# cc3100-breakout.net
KiCad netlist of a schematic drawn in EAGLE
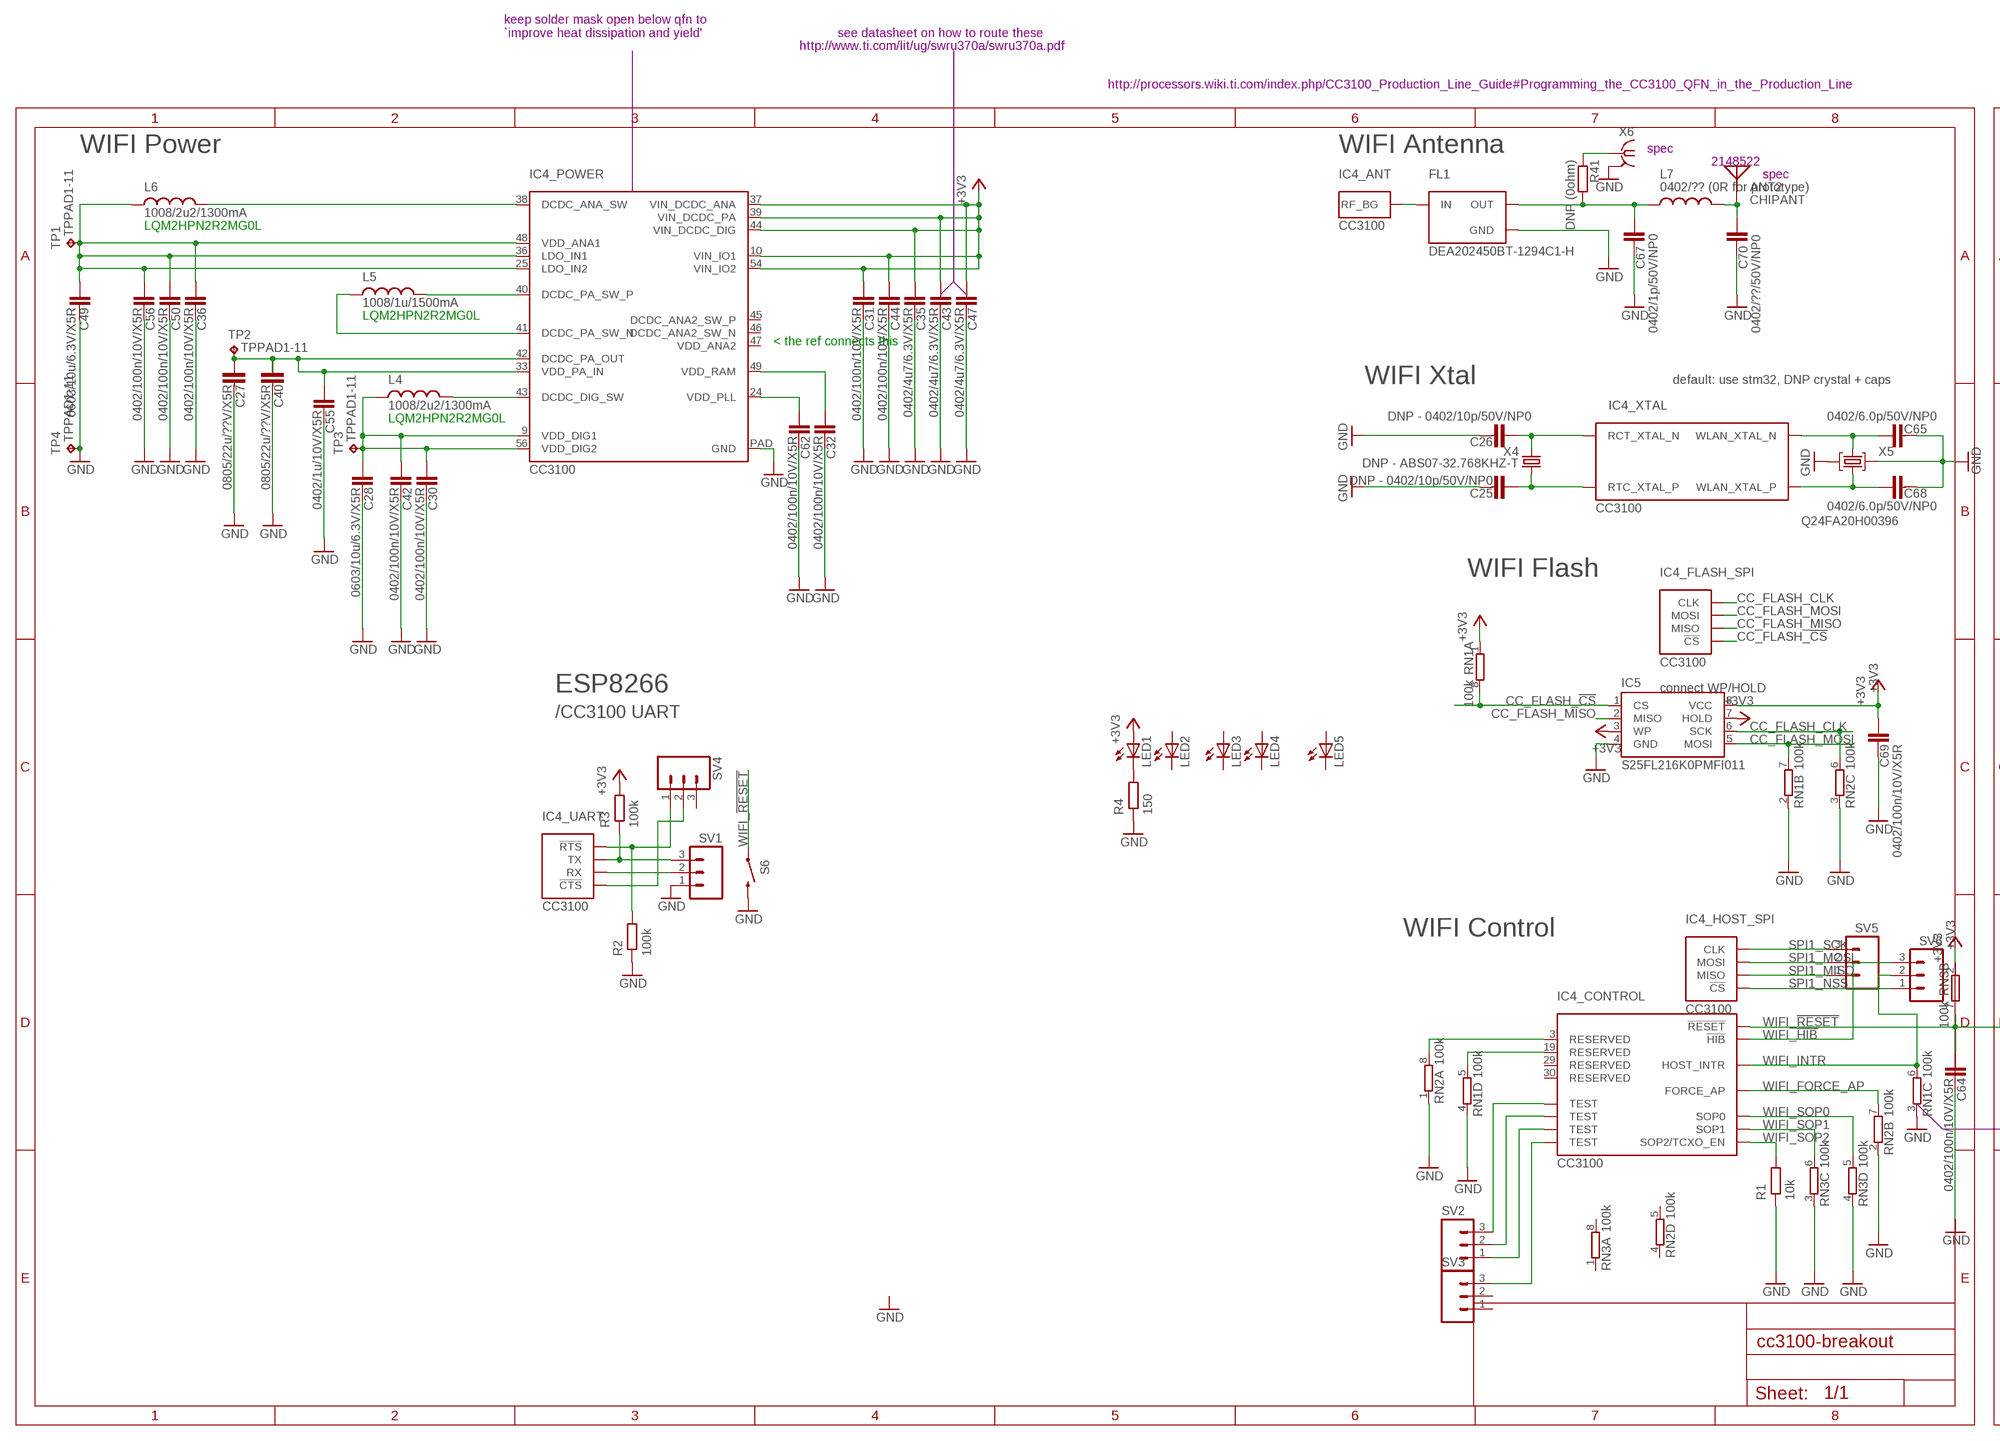
[diagram p0: schematic, sheet 1, part 1 of 2]
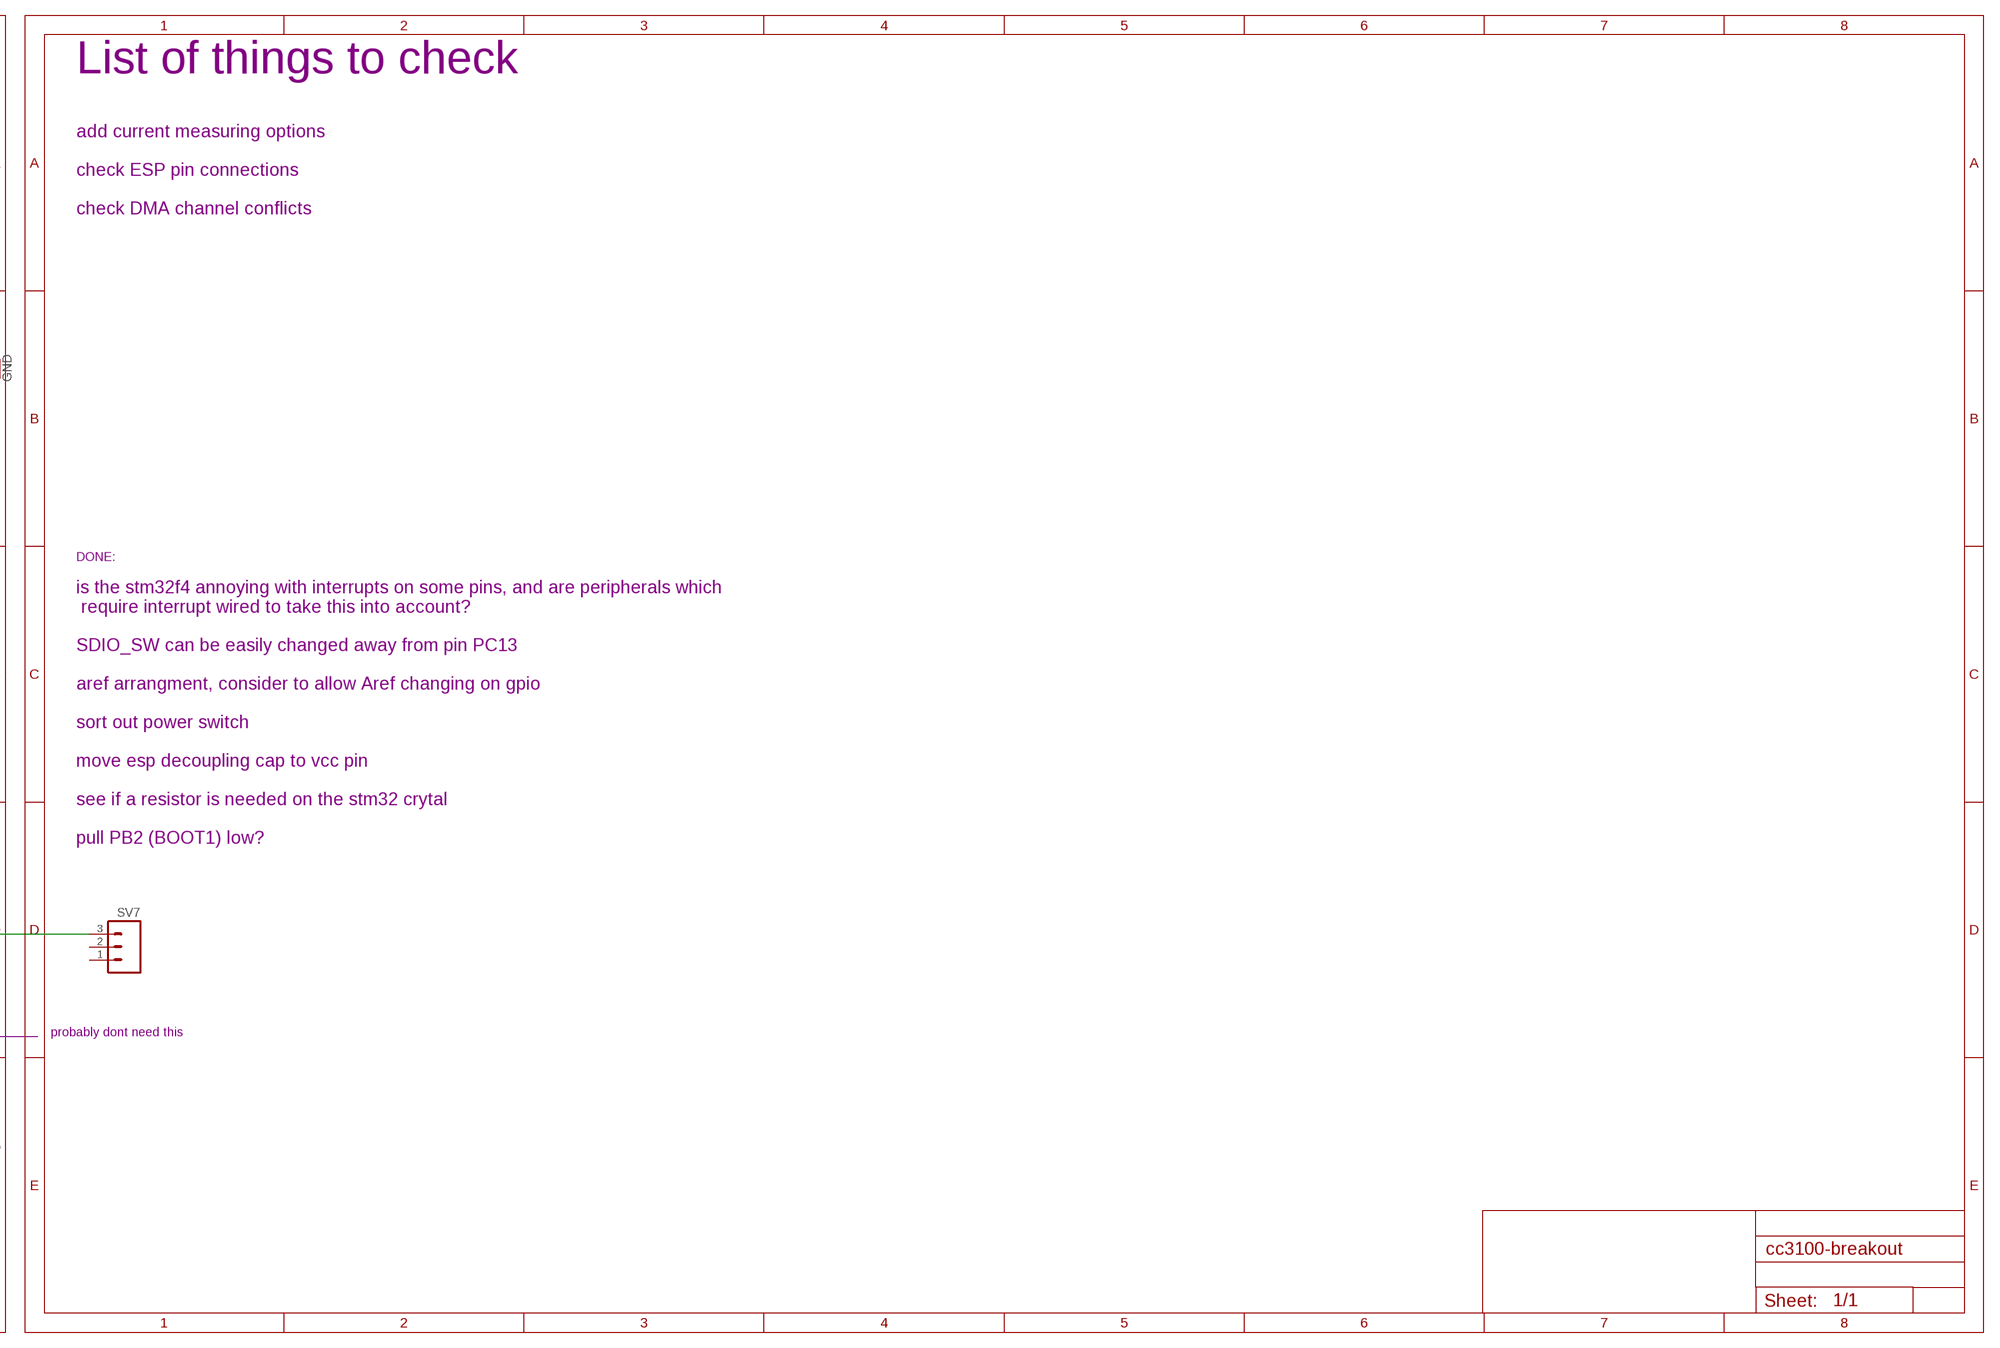
[diagram p1: schematic, sheet 1, part 2 of 2]

(export (version "E")
  (design (tool "Eeschema 10.0.6"))
  (components
    (comp (ref "ANT2")
      (value "CHIPANT")
      (footprint "eagle-import:2450AT42A100")
      (libsource (lib "eagle-import") (part "CHIPANT"))
    )
    (comp (ref "C25")
      (value "DNP - 0402/10p/50V/NP0")
      (footprint "eagle-import:C0603-N")
      (libsource (lib "eagle-import") (part "CAPACITOR0603-N"))
    )
    (comp (ref "C26")
      (value "DNP - 0402/10p/50V/NP0")
      (footprint "eagle-import:C0603-N")
      (libsource (lib "eagle-import") (part "CAPACITOR0603-N"))
    )
    (comp (ref "C27")
      (value "0805/22u/??V/X5R")
      (footprint "eagle-import:C0805-N")
      (libsource (lib "eagle-import") (part "CAPACITOR0805-N"))
    )
    (comp (ref "C28")
      (value "0603/10u/6.3V/X5R")
      (footprint "eagle-import:C0603K-SMALL")
      (libsource (lib "eagle-import") (part "C-EUC0603K-SMALL"))
    )
    (comp (ref "C30")
      (value "0402/100n/10V/X5R")
      (footprint "eagle-import:C0402-SMALLER")
      (libsource (lib "eagle-import") (part "C-EUC0402-SMALLER"))
    )
    (comp (ref "C31")
      (value "0402/100n/10V/X5R")
      (footprint "eagle-import:C0402-SMALLER")
      (libsource (lib "eagle-import") (part "C-EUC0402-SMALLER"))
    )
    (comp (ref "C32")
      (value "0402/100n/10V/X5R")
      (footprint "eagle-import:C0402-SMALLER")
      (libsource (lib "eagle-import") (part "C-EUC0402-SMALLER"))
    )
    (comp (ref "C35")
      (value "0402/4u7/6.3V/X5R")
      (footprint "eagle-import:C0402-SMALLER")
      (libsource (lib "eagle-import") (part "C-EUC0402-SMALLER"))
    )
    (comp (ref "C36")
      (value "0402/100n/10V/X5R")
      (footprint "eagle-import:C0402-SMALLER")
      (libsource (lib "eagle-import") (part "C-EUC0402-SMALLER"))
    )
    (comp (ref "C40")
      (value "0805/22u/??V/X5R")
      (footprint "eagle-import:C0805-N")
      (libsource (lib "eagle-import") (part "CAPACITOR0805-N"))
    )
    (comp (ref "C42")
      (value "0402/100n/10V/X5R")
      (footprint "eagle-import:C0402-SMALLER")
      (libsource (lib "eagle-import") (part "C-EUC0402-SMALLER"))
    )
    (comp (ref "C43")
      (value "0402/4u7/6.3V/X5R")
      (footprint "eagle-import:C0402-SMALLER")
      (libsource (lib "eagle-import") (part "C-EUC0402-SMALLER"))
    )
    (comp (ref "C44")
      (value "0402/100n/10V/X5R")
      (footprint "eagle-import:C0402-SMALLER")
      (libsource (lib "eagle-import") (part "C-EUC0402-SMALLER"))
    )
    (comp (ref "C47")
      (value "0402/4u7/6.3V/X5R")
      (footprint "eagle-import:C0402-SMALLER")
      (libsource (lib "eagle-import") (part "C-EUC0402-SMALLER"))
    )
    (comp (ref "C49")
      (value "0603/10u/6.3V/X5R")
      (footprint "eagle-import:C0603K-SMALL")
      (libsource (lib "eagle-import") (part "C-EUC0603K-SMALL"))
    )
    (comp (ref "C50")
      (value "0402/100n/10V/X5R")
      (footprint "eagle-import:C0402-SMALLER")
      (libsource (lib "eagle-import") (part "C-EUC0402-SMALLER"))
    )
    (comp (ref "C55")
      (value "0402/1u/10V/X5R")
      (footprint "eagle-import:C0402-SMALLER")
      (libsource (lib "eagle-import") (part "C-EUC0402-SMALLER"))
    )
    (comp (ref "C56")
      (value "0402/100n/10V/X5R")
      (footprint "eagle-import:C0402-SMALLER")
      (libsource (lib "eagle-import") (part "C-EUC0402-SMALLER"))
    )
    (comp (ref "C62")
      (value "0402/100n/10V/X5R")
      (footprint "eagle-import:C0402-SMALLER")
      (libsource (lib "eagle-import") (part "C-EUC0402-SMALLER"))
    )
    (comp (ref "C64")
      (value "0402/100n/10V/X5R")
      (footprint "eagle-import:C0402-SMALLER")
      (libsource (lib "eagle-import") (part "C-EUC0402-SMALLER"))
    )
    (comp (ref "C65")
      (value "0402/6.0p/50V/NP0")
      (footprint "eagle-import:C0603-N")
      (libsource (lib "eagle-import") (part "CAPACITOR0603-N"))
    )
    (comp (ref "C67")
      (value "0402/1p/50V/NP0")
      (footprint "eagle-import:C0402-SMALLER")
      (libsource (lib "eagle-import") (part "C-EUC0402-SMALLER"))
    )
    (comp (ref "C68")
      (value "0402/6.0p/50V/NP0")
      (footprint "eagle-import:C0603-N")
      (libsource (lib "eagle-import") (part "CAPACITOR0603-N"))
    )
    (comp (ref "C69")
      (value "0402/100n/10V/X5R")
      (footprint "eagle-import:C0402-SMALLER")
      (libsource (lib "eagle-import") (part "C-EUC0402-SMALLER"))
    )
    (comp (ref "C70")
      (value "0402/??/50V/NP0")
      (footprint "eagle-import:C0402-SMALLER")
      (libsource (lib "eagle-import") (part "C-EUC0402-SMALLER"))
    )
    (comp (ref "FL1")
      (value "DEA202450BT-1294C1-H")
      (footprint "eagle-import:DEA202450BT")
      (libsource (lib "eagle-import") (part "DEA202450BT-1294C1-H"))
    )
    (comp (ref "IC4")
      (value "CC3100")
      (footprint "eagle-import:VQFN-64")
      (libsource (lib "eagle-import") (part "CC3100"))
    )
    (comp (ref "IC5")
      (value "S25FL216K0PMFI011")
      (footprint "eagle-import:SO08-EIAJ")
      (libsource (lib "eagle-import") (part "SPI_FLASH-X25XXSMD1"))
    )
    (comp (ref "L4")
      (value "1008/2u2/1300mA")
      (footprint "eagle-import:1008")
      (libsource (lib "eagle-import") (part "INDUCTOR1008"))
    )
    (comp (ref "L5")
      (value "1008/1u/1500mA")
      (footprint "eagle-import:1008")
      (libsource (lib "eagle-import") (part "INDUCTOR1008"))
    )
    (comp (ref "L6")
      (value "1008/2u2/1300mA")
      (footprint "eagle-import:1008")
      (libsource (lib "eagle-import") (part "INDUCTOR1008"))
    )
    (comp (ref "L7")
      (value "0402/?? (0R for prototype)")
      (footprint "eagle-import:L0402")
      (libsource (lib "eagle-import") (part "INDUCTOR-0402-NARROW"))
    )
    (comp (ref "LED1")
      (value "LEDCHIPLED_0603")
      (footprint "eagle-import:CHIPLED_0603")
      (libsource (lib "eagle-import") (part "LEDCHIPLED_0603"))
    )
    (comp (ref "LED2")
      (value "LEDCHIPLED_0603")
      (footprint "eagle-import:CHIPLED_0603")
      (libsource (lib "eagle-import") (part "LEDCHIPLED_0603"))
    )
    (comp (ref "LED3")
      (value "LEDCHIPLED_0603")
      (footprint "eagle-import:CHIPLED_0603")
      (libsource (lib "eagle-import") (part "LEDCHIPLED_0603"))
    )
    (comp (ref "LED4")
      (value "LEDCHIPLED_0603")
      (footprint "eagle-import:CHIPLED_0603")
      (libsource (lib "eagle-import") (part "LEDCHIPLED_0603"))
    )
    (comp (ref "LED5")
      (value "LEDCHIPLED_0603")
      (footprint "eagle-import:CHIPLED_0603")
      (libsource (lib "eagle-import") (part "LEDCHIPLED_0603"))
    )
    (comp (ref "R1")
      (value "10k")
      (footprint "eagle-import:R0603-N")
      (libsource (lib "eagle-import") (part "RESISTOR0603-N"))
    )
    (comp (ref "R2")
      (value "100k")
      (footprint "eagle-import:R0603-N")
      (libsource (lib "eagle-import") (part "RESISTOR0603-N"))
    )
    (comp (ref "R3")
      (value "100k")
      (footprint "eagle-import:R0603-N")
      (libsource (lib "eagle-import") (part "RESISTOR0603-N"))
    )
    (comp (ref "R4")
      (value "150")
      (footprint "eagle-import:R0603-N")
      (libsource (lib "eagle-import") (part "RESISTOR0603-N"))
    )
    (comp (ref "R41")
      (value "DNP (0ohm)")
      (footprint "eagle-import:R0402-SMALLER")
      (libsource (lib "eagle-import") (part "R-EU_R0402-SMALLER"))
    )
    (comp (ref "RN1")
      (value "100k")
      (footprint "eagle-import:EXB38V")
      (libsource (lib "eagle-import") (part "4R-NEXB38V"))
    )
    (comp (ref "RN2")
      (value "100k")
      (footprint "eagle-import:EXB38V")
      (libsource (lib "eagle-import") (part "4R-NEXB38V"))
    )
    (comp (ref "RN3")
      (value "100k")
      (footprint "eagle-import:EXB38V")
      (libsource (lib "eagle-import") (part "4R-NEXB38V"))
    )
    (comp (ref "S6")
      (value "SWITCH-MOMENTARY-2SMD-1101NE")
      (footprint "eagle-import:TACTILE-SWITCH-1101NE")
      (libsource (lib "eagle-import") (part "SWITCH-MOMENTARY-2SMD-1101NE"))
    )
    (comp (ref "SV1")
      (value "M03PTH")
      (footprint "eagle-import:1X03")
      (libsource (lib "eagle-import") (part "M03PTH"))
    )
    (comp (ref "SV2")
      (value "M03PTH")
      (footprint "eagle-import:1X03")
      (libsource (lib "eagle-import") (part "M03PTH"))
    )
    (comp (ref "SV3")
      (value "M03PTH")
      (footprint "eagle-import:1X03")
      (libsource (lib "eagle-import") (part "M03PTH"))
    )
    (comp (ref "SV4")
      (value "M03PTH")
      (footprint "eagle-import:1X03")
      (libsource (lib "eagle-import") (part "M03PTH"))
    )
    (comp (ref "SV5")
      (value "M03PTH")
      (footprint "eagle-import:1X03")
      (libsource (lib "eagle-import") (part "M03PTH"))
    )
    (comp (ref "SV6")
      (value "M03PTH")
      (footprint "eagle-import:1X03")
      (libsource (lib "eagle-import") (part "M03PTH"))
    )
    (comp (ref "SV7")
      (value "M03PTH")
      (footprint "eagle-import:1X03")
      (libsource (lib "eagle-import") (part "M03PTH"))
    )
    (comp (ref "TP1")
      (value "TPPAD1-11")
      (footprint "eagle-import:P1-11")
      (libsource (lib "eagle-import") (part "TPPAD1-11"))
    )
    (comp (ref "TP2")
      (value "TPPAD1-11")
      (footprint "eagle-import:P1-11")
      (libsource (lib "eagle-import") (part "TPPAD1-11"))
    )
    (comp (ref "TP3")
      (value "TPPAD1-11")
      (footprint "eagle-import:P1-11")
      (libsource (lib "eagle-import") (part "TPPAD1-11"))
    )
    (comp (ref "TP4")
      (value "TPPAD1-11")
      (footprint "eagle-import:P1-11")
      (libsource (lib "eagle-import") (part "TPPAD1-11"))
    )
    (comp (ref "X4")
      (value "DNP - ABS07-32.768KHZ-T")
      (footprint "eagle-import:RESONATOR_EPSON_FC_145")
      (libsource (lib "eagle-import") (part "RESONATOR_EPSON_FC_145"))
    )
    (comp (ref "X5")
      (value "Q24FA20H00396")
      (footprint "eagle-import:CRYSTAL-2.5X2.0")
      (libsource (lib "eagle-import") (part "CRYSTAL-2.5X2.0"))
    )
    (comp (ref "X6")
      (value "MC-921")
      (footprint "eagle-import:MC-921")
      (libsource (lib "eagle-import") (part "MC-921"))
    )
  )
  (nets
    (net (code "1") (name "+3V3") (class "Default")
      (node (ref "C31") (pin "2") (pinfunction "2_2") (pintype "passive"))
      (node (ref "C35") (pin "2") (pinfunction "2_2") (pintype "passive"))
      (node (ref "C43") (pin "2") (pinfunction "2_2") (pintype "passive"))
      (node (ref "C44") (pin "2") (pinfunction "2_2") (pintype "passive"))
      (node (ref "C47") (pin "2") (pinfunction "2_2") (pintype "passive"))
      (node (ref "C69") (pin "2") (pinfunction "2_2") (pintype "passive"))
      (node (ref "IC4") (pin "10") (pinfunction "VIN_IO1_10") (pintype "bidirectional"))
      (node (ref "IC4") (pin "37") (pinfunction "VIN_DCDC_ANA_37") (pintype "bidirectional"))
      (node (ref "IC4") (pin "39") (pinfunction "VIN_DCDC_PA_39") (pintype "bidirectional"))
      (node (ref "IC4") (pin "44") (pinfunction "VIN_DCDC_DIG_44") (pintype "bidirectional"))
      (node (ref "IC4") (pin "54") (pinfunction "VIN_IO2_54") (pintype "bidirectional"))
      (node (ref "IC5") (pin "3") (pinfunction "WP_3") (pintype "bidirectional"))
      (node (ref "IC5") (pin "7") (pinfunction "HOLD_7") (pintype "bidirectional"))
      (node (ref "IC5") (pin "8") (pinfunction "VCC_8") (pintype "bidirectional"))
      (node (ref "LED1") (pin "A") (pinfunction "A_A") (pintype "passive"))
      (node (ref "R3") (pin "2") (pinfunction "P$2_2") (pintype "passive"))
      (node (ref "RN1") (pin "1") (pinfunction "1_1") (pintype "passive"))
      (node (ref "RN3") (pin "2") (pinfunction "1_2") (pintype "passive"))
    )
    (net (code "2") (name "/CC_FLASH_CLK") (class "Default")
      (node (ref "IC4") (pin "11") (pinfunction "CLK_11") (pintype "bidirectional"))
      (node (ref "IC5") (pin "6") (pinfunction "SCK_6") (pintype "bidirectional"))
      (node (ref "RN2") (pin "6") (pinfunction "2_6") (pintype "passive"))
    )
    (net (code "3") (name "/CC_FLASH_MISO") (class "Default")
      (node (ref "IC4") (pin "13") (pinfunction "MISO_13") (pintype "bidirectional"))
      (node (ref "IC5") (pin "2") (pinfunction "MISO_2") (pintype "bidirectional"))
    )
    (net (code "4") (name "/CC_FLASH_MOSI") (class "Default")
      (node (ref "IC4") (pin "12") (pinfunction "MOSI_12") (pintype "bidirectional"))
      (node (ref "IC5") (pin "5") (pinfunction "MOSI_5") (pintype "bidirectional"))
      (node (ref "RN1") (pin "7") (pinfunction "2_7") (pintype "passive"))
    )
    (net (code "5") (name "/CC_FLASH_~{CS}") (class "Default")
      (node (ref "IC4") (pin "14") (pinfunction "~{CS}_14") (pintype "bidirectional"))
      (node (ref "IC5") (pin "1") (pinfunction "CS_1") (pintype "bidirectional"))
      (node (ref "RN1") (pin "8") (pinfunction "2_8") (pintype "passive"))
    )
    (net (code "6") (name "/SPI1_MISO") (class "Default")
      (node (ref "IC4") (pin "7") (pinfunction "MISO_7") (pintype "bidirectional"))
      (node (ref "SV5") (pin "1") (pinfunction "1_1") (pintype "passive"))
    )
    (net (code "7") (name "/SPI1_MOSI") (class "Default")
      (node (ref "IC4") (pin "6") (pinfunction "MOSI_6") (pintype "bidirectional"))
      (node (ref "SV5") (pin "2") (pinfunction "2_2") (pintype "passive"))
    )
    (net (code "8") (name "/SPI1_NSS") (class "Default")
      (node (ref "IC4") (pin "8") (pinfunction "~{CS}_8") (pintype "bidirectional"))
      (node (ref "SV6") (pin "1") (pinfunction "1_1") (pintype "passive"))
    )
    (net (code "9") (name "/SPI1_SCK") (class "Default")
      (node (ref "IC4") (pin "5") (pinfunction "CLK_5") (pintype "bidirectional"))
      (node (ref "SV5") (pin "3") (pinfunction "3_3") (pintype "passive"))
    )
    (net (code "10") (name "/WIFI_FORCE_AP") (class "Default")
      (node (ref "IC4") (pin "4") (pinfunction "FORCE_AP_4") (pintype "bidirectional"))
      (node (ref "RN2") (pin "7") (pinfunction "2_7") (pintype "passive"))
    )
    (net (code "11") (name "/WIFI_INTR") (class "Default")
      (node (ref "IC4") (pin "15") (pinfunction "HOST_INTR_15") (pintype "bidirectional"))
      (node (ref "RN1") (pin "6") (pinfunction "2_6") (pintype "passive"))
      (node (ref "SV6") (pin "2") (pinfunction "2_2") (pintype "passive"))
    )
    (net (code "12") (name "/WIFI_SOP0") (class "Default")
      (node (ref "IC4") (pin "35") (pinfunction "SOP0_35") (pintype "bidirectional"))
      (node (ref "RN3") (pin "5") (pinfunction "2_5") (pintype "passive"))
    )
    (net (code "13") (name "/WIFI_SOP1") (class "Default")
      (node (ref "IC4") (pin "34") (pinfunction "SOP1_34") (pintype "bidirectional"))
      (node (ref "RN3") (pin "6") (pinfunction "2_6") (pintype "passive"))
    )
    (net (code "14") (name "/WIFI_SOP2") (class "Default")
      (node (ref "IC4") (pin "21") (pinfunction "SOP2/TCXO_EN_21") (pintype "bidirectional"))
      (node (ref "R1") (pin "2") (pinfunction "P$2_2") (pintype "passive"))
    )
    (net (code "15") (name "/WIFI_~{HIB}") (class "Default")
      (node (ref "IC4") (pin "2") (pinfunction "~{HIB}_2") (pintype "bidirectional"))
      (node (ref "SV6") (pin "3") (pinfunction "3_3") (pintype "passive"))
    )
    (net (code "16") (name "/WIFI_~{RESET}") (class "Default")
      (node (ref "C64") (pin "2") (pinfunction "2_2") (pintype "passive"))
      (node (ref "IC4") (pin "32") (pinfunction "~{RESET}_32") (pintype "bidirectional"))
      (node (ref "RN3") (pin "7") (pinfunction "2_7") (pintype "passive"))
      (node (ref "S6") (pin "1") (pinfunction "1_1") (pintype "passive"))
      (node (ref "SV7") (pin "3") (pinfunction "3_3") (pintype "passive"))
    )
    (net (code "17") (name "GND") (class "Default")
      (node (ref "C25") (pin "1") (pinfunction "1_1") (pintype "passive"))
      (node (ref "C26") (pin "1") (pinfunction "1_1") (pintype "passive"))
      (node (ref "C27") (pin "1") (pinfunction "1_1") (pintype "passive"))
      (node (ref "C28") (pin "1") (pinfunction "1_1") (pintype "passive"))
      (node (ref "C30") (pin "1") (pinfunction "1_1") (pintype "passive"))
      (node (ref "C31") (pin "1") (pinfunction "1_1") (pintype "passive"))
      (node (ref "C32") (pin "1") (pinfunction "1_1") (pintype "passive"))
      (node (ref "C35") (pin "1") (pinfunction "1_1") (pintype "passive"))
      (node (ref "C36") (pin "1") (pinfunction "1_1") (pintype "passive"))
      (node (ref "C40") (pin "1") (pinfunction "1_1") (pintype "passive"))
      (node (ref "C42") (pin "1") (pinfunction "1_1") (pintype "passive"))
      (node (ref "C43") (pin "1") (pinfunction "1_1") (pintype "passive"))
      (node (ref "C44") (pin "1") (pinfunction "1_1") (pintype "passive"))
      (node (ref "C47") (pin "1") (pinfunction "1_1") (pintype "passive"))
      (node (ref "C49") (pin "1") (pinfunction "1_1") (pintype "passive"))
      (node (ref "C50") (pin "1") (pinfunction "1_1") (pintype "passive"))
      (node (ref "C55") (pin "1") (pinfunction "1_1") (pintype "passive"))
      (node (ref "C56") (pin "1") (pinfunction "1_1") (pintype "passive"))
      (node (ref "C62") (pin "1") (pinfunction "1_1") (pintype "passive"))
      (node (ref "C64") (pin "1") (pinfunction "1_1") (pintype "passive"))
      (node (ref "C65") (pin "1") (pinfunction "1_1") (pintype "passive"))
      (node (ref "C67") (pin "2") (pinfunction "2_2") (pintype "passive"))
      (node (ref "C68") (pin "1") (pinfunction "1_1") (pintype "passive"))
      (node (ref "C69") (pin "1") (pinfunction "1_1") (pintype "passive"))
      (node (ref "C70") (pin "2") (pinfunction "2_2") (pintype "passive"))
      (node (ref "FL1") (pin "GND@2") (pinfunction "GND_GND@2") (pintype "bidirectional"))
      (node (ref "FL1") (pin "GND@4") (pinfunction "GND_GND@4") (pintype "bidirectional"))
      (node (ref "IC4") (pin "PAD") (pinfunction "GND_PAD") (pintype "bidirectional"))
      (node (ref "IC5") (pin "4") (pinfunction "GND_4") (pintype "bidirectional"))
      (node (ref "R1") (pin "1") (pinfunction "P$1_1") (pintype "passive"))
      (node (ref "R2") (pin "1") (pinfunction "P$1_1") (pintype "passive"))
      (node (ref "R4") (pin "1") (pinfunction "P$1_1") (pintype "passive"))
      (node (ref "RN1") (pin "2") (pinfunction "1_2") (pintype "passive"))
      (node (ref "RN1") (pin "3") (pinfunction "1_3") (pintype "passive"))
      (node (ref "RN1") (pin "4") (pinfunction "1_4") (pintype "passive"))
      (node (ref "RN2") (pin "1") (pinfunction "1_1") (pintype "passive"))
      (node (ref "RN2") (pin "2") (pinfunction "1_2") (pintype "passive"))
      (node (ref "RN2") (pin "3") (pinfunction "1_3") (pintype "passive"))
      (node (ref "RN3") (pin "3") (pinfunction "1_3") (pintype "passive"))
      (node (ref "RN3") (pin "4") (pinfunction "1_4") (pintype "passive"))
      (node (ref "S6") (pin "2") (pinfunction "2_2") (pintype "passive"))
      (node (ref "SV1") (pin "1") (pinfunction "1_1") (pintype "passive"))
      (node (ref "TP4") (pin "TP") (pinfunction "TP_TP") (pintype "input"))
      (node (ref "X5") (pin "2") (pinfunction "GND_2") (pintype "passive"))
      (node (ref "X5") (pin "4") (pinfunction "GND_4") (pintype "passive"))
      (node (ref "X6") (pin "2@1") (pinfunction "GND_2@1") (pintype "passive"))
      (node (ref "X6") (pin "2@2") (pinfunction "GND_2@2") (pintype "passive"))
    )
    (net (code "18") (name "Net-(ANT2-1)") (class "Default")
      (node (ref "ANT2") (pin "P$1") (pinfunction "1_P$1") (pintype "passive"))
      (node (ref "C70") (pin "1") (pinfunction "1_1") (pintype "passive"))
      (node (ref "L7") (pin "2") (pinfunction "2_2") (pintype "passive"))
    )
    (net (code "19") (name "Net-(C67-Pad1)") (class "Default")
      (node (ref "C67") (pin "1") (pinfunction "1_1") (pintype "passive"))
      (node (ref "FL1") (pin "OUT") (pinfunction "OUT_OUT") (pintype "bidirectional"))
      (node (ref "L7") (pin "1") (pinfunction "1_1") (pintype "passive"))
      (node (ref "R41") (pin "2") (pinfunction "2_2") (pintype "passive"))
    )
    (net (code "20") (name "Net-(IC4A-RF_BG)") (class "Default")
      (node (ref "FL1") (pin "IN") (pinfunction "IN_IN") (pintype "bidirectional"))
      (node (ref "IC4") (pin "31") (pinfunction "RF_BG_31") (pintype "bidirectional"))
    )
    (net (code "21") (name "Net-(IC4B-TEST-Pad58)") (class "Default")
      (node (ref "IC4") (pin "58") (pinfunction "TEST_58") (pintype "bidirectional"))
      (node (ref "SV2") (pin "3") (pinfunction "3_3") (pintype "passive"))
    )
    (net (code "22") (name "Net-(IC4B-TEST-Pad59)") (class "Default")
      (node (ref "IC4") (pin "59") (pinfunction "TEST_59") (pintype "bidirectional"))
      (node (ref "SV2") (pin "2") (pinfunction "2_2") (pintype "passive"))
    )
    (net (code "23") (name "Net-(IC4B-TEST-Pad60)") (class "Default")
      (node (ref "IC4") (pin "60") (pinfunction "TEST_60") (pintype "bidirectional"))
      (node (ref "SV2") (pin "1") (pinfunction "1_1") (pintype "passive"))
    )
    (net (code "24") (name "Net-(IC4B-TEST-Pad62)") (class "Default")
      (node (ref "IC4") (pin "62") (pinfunction "TEST_62") (pintype "bidirectional"))
      (node (ref "SV3") (pin "3") (pinfunction "3_3") (pintype "passive"))
    )
    (net (code "25") (name "Net-(IC4E-DCDC_ANA_SW)") (class "Default")
      (node (ref "IC4") (pin "38") (pinfunction "DCDC_ANA_SW_38") (pintype "bidirectional"))
      (node (ref "L6") (pin "2") (pinfunction "2_2") (pintype "passive"))
    )
    (net (code "26") (name "Net-(IC4E-DCDC_DIG_SW)") (class "Default")
      (node (ref "IC4") (pin "43") (pinfunction "DCDC_DIG_SW_43") (pintype "bidirectional"))
      (node (ref "L4") (pin "2") (pinfunction "2_2") (pintype "passive"))
    )
    (net (code "27") (name "Net-(IC4E-DCDC_PA_OUT)") (class "Default")
      (node (ref "C27") (pin "2") (pinfunction "2_2") (pintype "passive"))
      (node (ref "C40") (pin "2") (pinfunction "2_2") (pintype "passive"))
      (node (ref "C55") (pin "2") (pinfunction "2_2") (pintype "passive"))
      (node (ref "IC4") (pin "33") (pinfunction "VDD_PA_IN_33") (pintype "bidirectional"))
      (node (ref "IC4") (pin "42") (pinfunction "DCDC_PA_OUT_42") (pintype "bidirectional"))
      (node (ref "TP2") (pin "TP") (pinfunction "TP_TP") (pintype "input"))
    )
    (net (code "28") (name "Net-(IC4E-DCDC_PA_SW_N)") (class "Default")
      (node (ref "IC4") (pin "41") (pinfunction "DCDC_PA_SW_N_41") (pintype "bidirectional"))
      (node (ref "L5") (pin "1") (pinfunction "1_1") (pintype "passive"))
    )
    (net (code "29") (name "Net-(IC4E-DCDC_PA_SW_P)") (class "Default")
      (node (ref "IC4") (pin "40") (pinfunction "DCDC_PA_SW_P_40") (pintype "bidirectional"))
      (node (ref "L5") (pin "2") (pinfunction "2_2") (pintype "passive"))
    )
    (net (code "30") (name "Net-(IC4E-LDO_IN1)") (class "Default")
      (node (ref "C36") (pin "2") (pinfunction "2_2") (pintype "passive"))
      (node (ref "C49") (pin "2") (pinfunction "2_2") (pintype "passive"))
      (node (ref "C50") (pin "2") (pinfunction "2_2") (pintype "passive"))
      (node (ref "C56") (pin "2") (pinfunction "2_2") (pintype "passive"))
      (node (ref "IC4") (pin "25") (pinfunction "LDO_IN2_25") (pintype "bidirectional"))
      (node (ref "IC4") (pin "36") (pinfunction "LDO_IN1_36") (pintype "bidirectional"))
      (node (ref "IC4") (pin "48") (pinfunction "VDD_ANA1_48") (pintype "bidirectional"))
      (node (ref "L6") (pin "1") (pinfunction "1_1") (pintype "passive"))
      (node (ref "TP1") (pin "TP") (pinfunction "TP_TP") (pintype "input"))
    )
    (net (code "31") (name "Net-(IC4E-VDD_DIG1)") (class "Default")
      (node (ref "C28") (pin "2") (pinfunction "2_2") (pintype "passive"))
      (node (ref "C30") (pin "2") (pinfunction "2_2") (pintype "passive"))
      (node (ref "C42") (pin "2") (pinfunction "2_2") (pintype "passive"))
      (node (ref "IC4") (pin "56") (pinfunction "VDD_DIG2_56") (pintype "bidirectional"))
      (node (ref "IC4") (pin "9") (pinfunction "VDD_DIG1_9") (pintype "bidirectional"))
      (node (ref "L4") (pin "1") (pinfunction "1_1") (pintype "passive"))
      (node (ref "TP3") (pin "TP") (pinfunction "TP_TP") (pintype "input"))
    )
    (net (code "32") (name "Net-(IC4E-VDD_PLL)") (class "Default")
      (node (ref "C62") (pin "2") (pinfunction "2_2") (pintype "passive"))
      (node (ref "IC4") (pin "24") (pinfunction "VDD_PLL_24") (pintype "bidirectional"))
    )
    (net (code "33") (name "Net-(IC4E-VDD_RAM)") (class "Default")
      (node (ref "C32") (pin "2") (pinfunction "2_2") (pintype "passive"))
      (node (ref "IC4") (pin "49") (pinfunction "VDD_RAM_49") (pintype "bidirectional"))
    )
    (net (code "34") (name "Net-(IC4F-RX)") (class "Default")
      (node (ref "IC4") (pin "57") (pinfunction "RX_57") (pintype "bidirectional"))
      (node (ref "SV1") (pin "2") (pinfunction "2_2") (pintype "passive"))
    )
    (net (code "35") (name "Net-(IC4F-TX)") (class "Default")
      (node (ref "IC4") (pin "55") (pinfunction "TX_55") (pintype "bidirectional"))
      (node (ref "R3") (pin "1") (pinfunction "P$1_1") (pintype "passive"))
      (node (ref "SV1") (pin "3") (pinfunction "3_3") (pintype "passive"))
    )
    (net (code "36") (name "Net-(IC4F-~{CTS})") (class "Default")
      (node (ref "IC4") (pin "61") (pinfunction "~{CTS}_61") (pintype "bidirectional"))
      (node (ref "SV4") (pin "2") (pinfunction "2_2") (pintype "passive"))
    )
    (net (code "37") (name "Net-(IC4F-~{RTS})") (class "Default")
      (node (ref "IC4") (pin "50") (pinfunction "~{RTS}_50") (pintype "bidirectional"))
      (node (ref "R2") (pin "2") (pinfunction "P$2_2") (pintype "passive"))
      (node (ref "SV4") (pin "1") (pinfunction "1_1") (pintype "passive"))
    )
    (net (code "38") (name "Net-(IC4G-RCT_XTAL_N)") (class "Default")
      (node (ref "C26") (pin "2") (pinfunction "2_2") (pintype "passive"))
      (node (ref "IC4") (pin "52") (pinfunction "RCT_XTAL_N_52") (pintype "bidirectional"))
      (node (ref "X4") (pin "P$1") (pinfunction "1_P$1") (pintype "bidirectional"))
    )
    (net (code "39") (name "Net-(IC4G-RTC_XTAL_P)") (class "Default")
      (node (ref "C25") (pin "2") (pinfunction "2_2") (pintype "passive"))
      (node (ref "IC4") (pin "51") (pinfunction "RTC_XTAL_P_51") (pintype "bidirectional"))
      (node (ref "X4") (pin "P$2") (pinfunction "2_P$2") (pintype "bidirectional"))
    )
    (net (code "40") (name "Net-(IC4G-WLAN_XTAL_N)") (class "Default")
      (node (ref "C65") (pin "2") (pinfunction "2_2") (pintype "passive"))
      (node (ref "IC4") (pin "22") (pinfunction "WLAN_XTAL_N_22") (pintype "bidirectional"))
      (node (ref "X5") (pin "3") (pinfunction "C2_3") (pintype "passive"))
    )
    (net (code "41") (name "Net-(IC4G-WLAN_XTAL_P)") (class "Default")
      (node (ref "C68") (pin "2") (pinfunction "2_2") (pintype "passive"))
      (node (ref "IC4") (pin "23") (pinfunction "WLAN_XTAL_P_23") (pintype "bidirectional"))
      (node (ref "X5") (pin "1") (pinfunction "C1_1") (pintype "passive"))
    )
    (net (code "42") (name "Net-(R4-P$2)") (class "Default")
      (node (ref "LED1") (pin "C") (pinfunction "C_C") (pintype "passive"))
      (node (ref "R4") (pin "2") (pinfunction "P$2_2") (pintype "passive"))
    )
    (net (code "43") (name "Net-(R41-Pad1)") (class "Default")
      (node (ref "R41") (pin "1") (pinfunction "1_1") (pintype "passive"))
      (node (ref "X6") (pin "1") (pinfunction "1_1") (pintype "passive"))
    )
    (net (code "44") (name "Net-(RN1D-2)") (class "Default")
      (node (ref "IC4") (pin "19") (pinfunction "RESERVED_19") (pintype "bidirectional"))
      (node (ref "RN1") (pin "5") (pinfunction "2_5") (pintype "passive"))
    )
    (net (code "45") (name "Net-(RN2A-2)") (class "Default")
      (node (ref "IC4") (pin "3") (pinfunction "RESERVED_3") (pintype "bidirectional"))
      (node (ref "RN2") (pin "8") (pinfunction "2_8") (pintype "passive"))
    )
    (net (code "46") (name "unconnected-(IC4B-RESERVED-Pad29)") (class "Default")
      (node (ref "IC4") (pin "29") (pinfunction "RESERVED_29") (pintype "bidirectional"))
    )
    (net (code "47") (name "unconnected-(IC4B-RESERVED-Pad30)") (class "Default")
      (node (ref "IC4") (pin "30") (pinfunction "RESERVED_30") (pintype "bidirectional"))
    )
    (net (code "48") (name "unconnected-(IC4E-DCDC_ANA2_SW_N-Pad46)") (class "Default")
      (node (ref "IC4") (pin "46") (pinfunction "DCDC_ANA2_SW_N_46") (pintype "bidirectional"))
    )
    (net (code "49") (name "unconnected-(IC4E-DCDC_ANA2_SW_P-Pad45)") (class "Default")
      (node (ref "IC4") (pin "45") (pinfunction "DCDC_ANA2_SW_P_45") (pintype "bidirectional"))
    )
    (net (code "50") (name "unconnected-(IC4E-VDD_ANA2-Pad47)") (class "Default")
      (node (ref "IC4") (pin "47") (pinfunction "VDD_ANA2_47") (pintype "bidirectional"))
    )
    (net (code "51") (name "unconnected-(LED2-PadA)") (class "Default")
      (node (ref "LED2") (pin "A") (pinfunction "A_A") (pintype "passive"))
    )
    (net (code "52") (name "unconnected-(LED2-PadC)") (class "Default")
      (node (ref "LED2") (pin "C") (pinfunction "C_C") (pintype "passive"))
    )
    (net (code "53") (name "unconnected-(LED3-PadA)") (class "Default")
      (node (ref "LED3") (pin "A") (pinfunction "A_A") (pintype "passive"))
    )
    (net (code "54") (name "unconnected-(LED3-PadC)") (class "Default")
      (node (ref "LED3") (pin "C") (pinfunction "C_C") (pintype "passive"))
    )
    (net (code "55") (name "unconnected-(LED4-PadA)") (class "Default")
      (node (ref "LED4") (pin "A") (pinfunction "A_A") (pintype "passive"))
    )
    (net (code "56") (name "unconnected-(LED4-PadC)") (class "Default")
      (node (ref "LED4") (pin "C") (pinfunction "C_C") (pintype "passive"))
    )
    (net (code "57") (name "unconnected-(LED5-PadA)") (class "Default")
      (node (ref "LED5") (pin "A") (pinfunction "A_A") (pintype "passive"))
    )
    (net (code "58") (name "unconnected-(LED5-PadC)") (class "Default")
      (node (ref "LED5") (pin "C") (pinfunction "C_C") (pintype "passive"))
    )
    (net (code "59") (name "unconnected-(RN2D-1-Pad4)") (class "Default")
      (node (ref "RN2") (pin "4") (pinfunction "1_4") (pintype "passive"))
    )
    (net (code "60") (name "unconnected-(RN2D-2-Pad5)") (class "Default")
      (node (ref "RN2") (pin "5") (pinfunction "2_5") (pintype "passive"))
    )
    (net (code "61") (name "unconnected-(RN3-Pad1)") (class "Default")
      (node (ref "RN3") (pin "1") (pinfunction "1_1") (pintype "passive"))
    )
    (net (code "62") (name "unconnected-(RN3A-2-Pad8)") (class "Default")
      (node (ref "RN3") (pin "8") (pinfunction "2_8") (pintype "passive"))
    )
    (net (code "63") (name "unconnected-(SV3-Pad1)") (class "Default")
      (node (ref "SV3") (pin "1") (pinfunction "1_1") (pintype "passive"))
    )
    (net (code "64") (name "unconnected-(SV3-Pad2)") (class "Default")
      (node (ref "SV3") (pin "2") (pinfunction "2_2") (pintype "passive"))
    )
    (net (code "65") (name "unconnected-(SV4-Pad3)") (class "Default")
      (node (ref "SV4") (pin "3") (pinfunction "3_3") (pintype "passive"))
    )
    (net (code "66") (name "unconnected-(SV7-Pad1)") (class "Default")
      (node (ref "SV7") (pin "1") (pinfunction "1_1") (pintype "passive"))
    )
    (net (code "67") (name "unconnected-(SV7-Pad2)") (class "Default")
      (node (ref "SV7") (pin "2") (pinfunction "2_2") (pintype "passive"))
    )
  )
)
